# blinkm_mk2v5.net
KiCad netlist of a schematic drawn in EAGLE
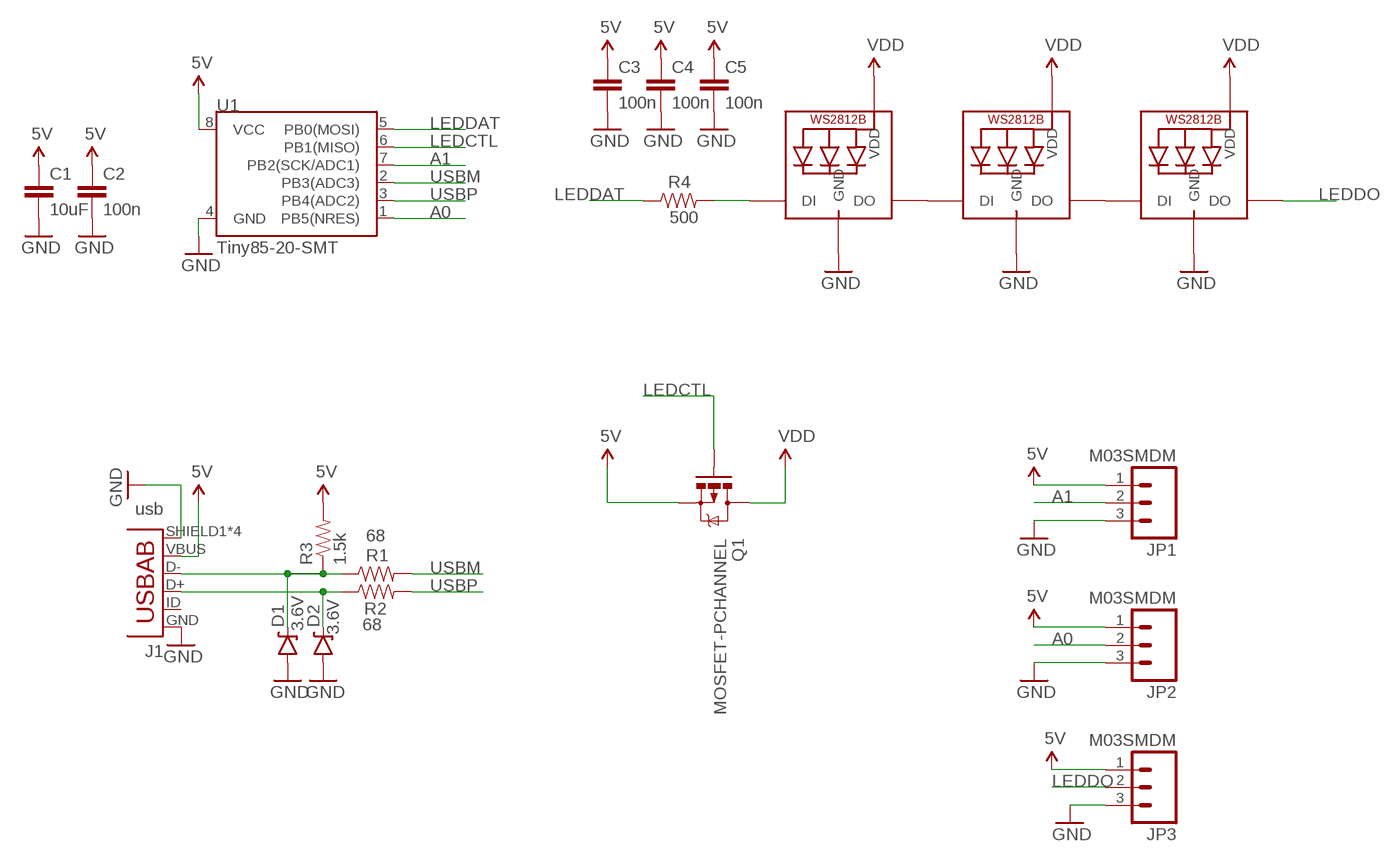
[diagram p0: schematic, sheet 1]

(export (version "E")
  (design (tool "Eeschema 10.0.6"))
  (components
    (comp (ref "C1")
      (value "10uF")
      (footprint "eagle-import:0603-CAP")
      (libsource (lib "eagle-import") (part "CAP0603-CAP"))
    )
    (comp (ref "C2")
      (value "100n")
      (footprint "eagle-import:0603-CAP")
      (libsource (lib "eagle-import") (part "CAP0603-CAP"))
    )
    (comp (ref "C3")
      (value "100n")
      (footprint "eagle-import:0603-CAP")
      (libsource (lib "eagle-import") (part "CAP0603-CAP"))
    )
    (comp (ref "C4")
      (value "100n")
      (footprint "eagle-import:0603-CAP")
      (libsource (lib "eagle-import") (part "CAP0603-CAP"))
    )
    (comp (ref "C5")
      (value "100n")
      (footprint "eagle-import:0603-CAP")
      (libsource (lib "eagle-import") (part "CAP0603-CAP"))
    )
    (comp (ref "D1")
      (value "3.6V")
      (footprint "eagle-import:SOD-323")
      (libsource (lib "eagle-import") (part "DIODE-ZENER3.3V"))
    )
    (comp (ref "D2")
      (value "3.6V")
      (footprint "eagle-import:SOD-323")
      (libsource (lib "eagle-import") (part "DIODE-ZENER3.3V"))
    )
    (comp (ref "J1")
      (value "usb")
      (footprint "eagle-import:USB-AB-MICRO-SMD")
      (libsource (lib "eagle-import") (part "USB-AB"))
    )
    (comp (ref "JP1")
      (value "M03SMDM")
      (footprint "eagle-import:1X03-SMD-MINIMAL")
      (libsource (lib "eagle-import") (part "M03SMDM"))
    )
    (comp (ref "JP2")
      (value "M03SMDM")
      (footprint "eagle-import:1X03-SMD-MINIMAL")
      (libsource (lib "eagle-import") (part "M03SMDM"))
    )
    (comp (ref "JP3")
      (value "M03SMDM")
      (footprint "eagle-import:1X03-SMD-MINIMAL")
      (libsource (lib "eagle-import") (part "M03SMDM"))
    )
    (comp (ref "LED1")
      (value "WS2812B3535")
      (footprint "eagle-import:LED3535")
      (libsource (lib "eagle-import") (part "WS2812B3535"))
    )
    (comp (ref "LED2")
      (value "WS2812B3535")
      (footprint "eagle-import:LED3535")
      (libsource (lib "eagle-import") (part "WS2812B3535"))
    )
    (comp (ref "LED3")
      (value "WS2812B3535")
      (footprint "eagle-import:LED3535")
      (libsource (lib "eagle-import") (part "WS2812B3535"))
    )
    (comp (ref "Q1")
      (value "MOSFET-PCHANNEL")
      (footprint "eagle-import:SOT23-3")
      (libsource (lib "eagle-import") (part "MOSFET-PCHANNEL"))
    )
    (comp (ref "R1")
      (value "68")
      (footprint "eagle-import:0603-RES")
      (libsource (lib "eagle-import") (part "RESISTOR0603-RES"))
    )
    (comp (ref "R2")
      (value "68")
      (footprint "eagle-import:0603-RES")
      (libsource (lib "eagle-import") (part "RESISTOR0603-RES"))
    )
    (comp (ref "R3")
      (value "1.5k")
      (footprint "eagle-import:0603-RES")
      (libsource (lib "eagle-import") (part "RESISTOR0603-RES"))
    )
    (comp (ref "R4")
      (value "500")
      (footprint "eagle-import:0603-RES")
      (libsource (lib "eagle-import") (part "RESISTOR0603-RES"))
    )
    (comp (ref "U1")
      (value "Tiny85-20-SMT")
      (footprint "eagle-import:SO08-EIAJ")
      (libsource (lib "eagle-import") (part "ATTINY45TINY85-20-SMT"))
    )
  )
  (nets
    (net (code "1") (name "/A0") (class "Default")
      (node (ref "JP2") (pin "2") (pinfunction "2_2") (pintype "passive"))
      (node (ref "U1") (pin "1") (pinfunction "PB5(NRES)_1") (pintype "bidirectional"))
    )
    (net (code "2") (name "/A1") (class "Default")
      (node (ref "JP1") (pin "2") (pinfunction "2_2") (pintype "passive"))
      (node (ref "U1") (pin "7") (pinfunction "PB2(SCK/ADC1)_7") (pintype "bidirectional"))
    )
    (net (code "3") (name "/LEDCTL") (class "Default")
      (node (ref "Q1") (pin "1") (pinfunction "G_1") (pintype "passive"))
      (node (ref "U1") (pin "6") (pinfunction "PB1(MISO)_6") (pintype "bidirectional"))
    )
    (net (code "4") (name "/LEDDAT") (class "Default")
      (node (ref "R4") (pin "1") (pinfunction "1_1") (pintype "passive"))
      (node (ref "U1") (pin "5") (pinfunction "PB0(MOSI)_5") (pintype "bidirectional"))
    )
    (net (code "5") (name "/LEDDO") (class "Default")
      (node (ref "JP3") (pin "2") (pinfunction "2_2") (pintype "passive"))
      (node (ref "LED3") (pin "3") (pinfunction "DO_3") (pintype "output"))
    )
    (net (code "6") (name "/USBM") (class "Default")
      (node (ref "R1") (pin "2") (pinfunction "2_2") (pintype "passive"))
      (node (ref "U1") (pin "2") (pinfunction "PB3(ADC3)_2") (pintype "bidirectional"))
    )
    (net (code "7") (name "/USBP") (class "Default")
      (node (ref "R2") (pin "2") (pinfunction "2_2") (pintype "passive"))
      (node (ref "U1") (pin "3") (pinfunction "PB4(ADC2)_3") (pintype "bidirectional"))
    )
    (net (code "8") (name "5V") (class "Default")
      (node (ref "C1") (pin "1") (pinfunction "1_1") (pintype "passive"))
      (node (ref "C2") (pin "1") (pinfunction "1_1") (pintype "passive"))
      (node (ref "C3") (pin "1") (pinfunction "1_1") (pintype "passive"))
      (node (ref "C4") (pin "1") (pinfunction "1_1") (pintype "passive"))
      (node (ref "C5") (pin "1") (pinfunction "1_1") (pintype "passive"))
      (node (ref "J1") (pin "VBUS") (pinfunction "VBUS_VBUS") (pintype "bidirectional"))
      (node (ref "JP1") (pin "1") (pinfunction "1_1") (pintype "passive"))
      (node (ref "JP2") (pin "1") (pinfunction "1_1") (pintype "passive"))
      (node (ref "JP3") (pin "1") (pinfunction "1_1") (pintype "passive"))
      (node (ref "Q1") (pin "2") (pinfunction "S_2") (pintype "passive"))
      (node (ref "R3") (pin "2") (pinfunction "2_2") (pintype "passive"))
      (node (ref "U1") (pin "8") (pinfunction "VCC_8") (pintype "bidirectional"))
    )
    (net (code "9") (name "GND") (class "Default")
      (node (ref "C1") (pin "2") (pinfunction "2_2") (pintype "passive"))
      (node (ref "C2") (pin "2") (pinfunction "2_2") (pintype "passive"))
      (node (ref "C3") (pin "2") (pinfunction "2_2") (pintype "passive"))
      (node (ref "C4") (pin "2") (pinfunction "2_2") (pintype "passive"))
      (node (ref "C5") (pin "2") (pinfunction "2_2") (pintype "passive"))
      (node (ref "D1") (pin "A") (pinfunction "A_A") (pintype "passive"))
      (node (ref "D2") (pin "A") (pinfunction "A_A") (pintype "passive"))
      (node (ref "J1") (pin "GND") (pinfunction "GND_GND") (pintype "bidirectional"))
      (node (ref "J1") (pin "SHIELD1") (pinfunction "SHIELD_SHIELD1") (pintype "bidirectional"))
      (node (ref "J1") (pin "SHIELD2") (pinfunction "SHIELD_SHIELD2") (pintype "bidirectional"))
      (node (ref "J1") (pin "SHIELD3") (pinfunction "SHIELD_SHIELD3") (pintype "bidirectional"))
      (node (ref "J1") (pin "SHIELD4") (pinfunction "SHIELD_SHIELD4") (pintype "bidirectional"))
      (node (ref "JP1") (pin "3") (pinfunction "3_3") (pintype "passive"))
      (node (ref "JP2") (pin "3") (pinfunction "3_3") (pintype "passive"))
      (node (ref "JP3") (pin "3") (pinfunction "3_3") (pintype "passive"))
      (node (ref "LED1") (pin "4") (pinfunction "GND_4") (pintype "power_in"))
      (node (ref "LED2") (pin "4") (pinfunction "GND_4") (pintype "power_in"))
      (node (ref "LED3") (pin "4") (pinfunction "GND_4") (pintype "power_in"))
      (node (ref "U1") (pin "4") (pinfunction "GND_4") (pintype "bidirectional"))
    )
    (net (code "10") (name "Net-(D1-PadC)") (class "Default")
      (node (ref "D1") (pin "C") (pinfunction "C_C") (pintype "passive"))
      (node (ref "J1") (pin "D-") (pinfunction "D-_D-") (pintype "bidirectional"))
      (node (ref "R1") (pin "1") (pinfunction "1_1") (pintype "passive"))
      (node (ref "R3") (pin "1") (pinfunction "1_1") (pintype "passive"))
    )
    (net (code "11") (name "Net-(D2-PadC)") (class "Default")
      (node (ref "D2") (pin "C") (pinfunction "C_C") (pintype "passive"))
      (node (ref "J1") (pin "D+") (pinfunction "D+_D+") (pintype "bidirectional"))
      (node (ref "R2") (pin "1") (pinfunction "1_1") (pintype "passive"))
    )
    (net (code "12") (name "Net-(LED1-DI)") (class "Default")
      (node (ref "LED1") (pin "1") (pinfunction "DI_1") (pintype "input"))
      (node (ref "R4") (pin "2") (pinfunction "2_2") (pintype "passive"))
    )
    (net (code "13") (name "Net-(LED1-DO)") (class "Default")
      (node (ref "LED1") (pin "3") (pinfunction "DO_3") (pintype "output"))
      (node (ref "LED2") (pin "1") (pinfunction "DI_1") (pintype "input"))
    )
    (net (code "14") (name "Net-(LED2-DO)") (class "Default")
      (node (ref "LED2") (pin "3") (pinfunction "DO_3") (pintype "output"))
      (node (ref "LED3") (pin "1") (pinfunction "DI_1") (pintype "input"))
    )
    (net (code "15") (name "VDD") (class "Default")
      (node (ref "LED1") (pin "2") (pinfunction "VDD_2") (pintype "power_in"))
      (node (ref "LED2") (pin "2") (pinfunction "VDD_2") (pintype "power_in"))
      (node (ref "LED3") (pin "2") (pinfunction "VDD_2") (pintype "power_in"))
      (node (ref "Q1") (pin "3") (pinfunction "D_3") (pintype "passive"))
    )
    (net (code "16") (name "unconnected-(J1-USBID-PadID)") (class "Default")
      (node (ref "J1") (pin "ID") (pinfunction "USBID_ID") (pintype "bidirectional"))
    )
  )
)
